# ADS8866.net
KiCad netlist of a schematic drawn in Altium Designer
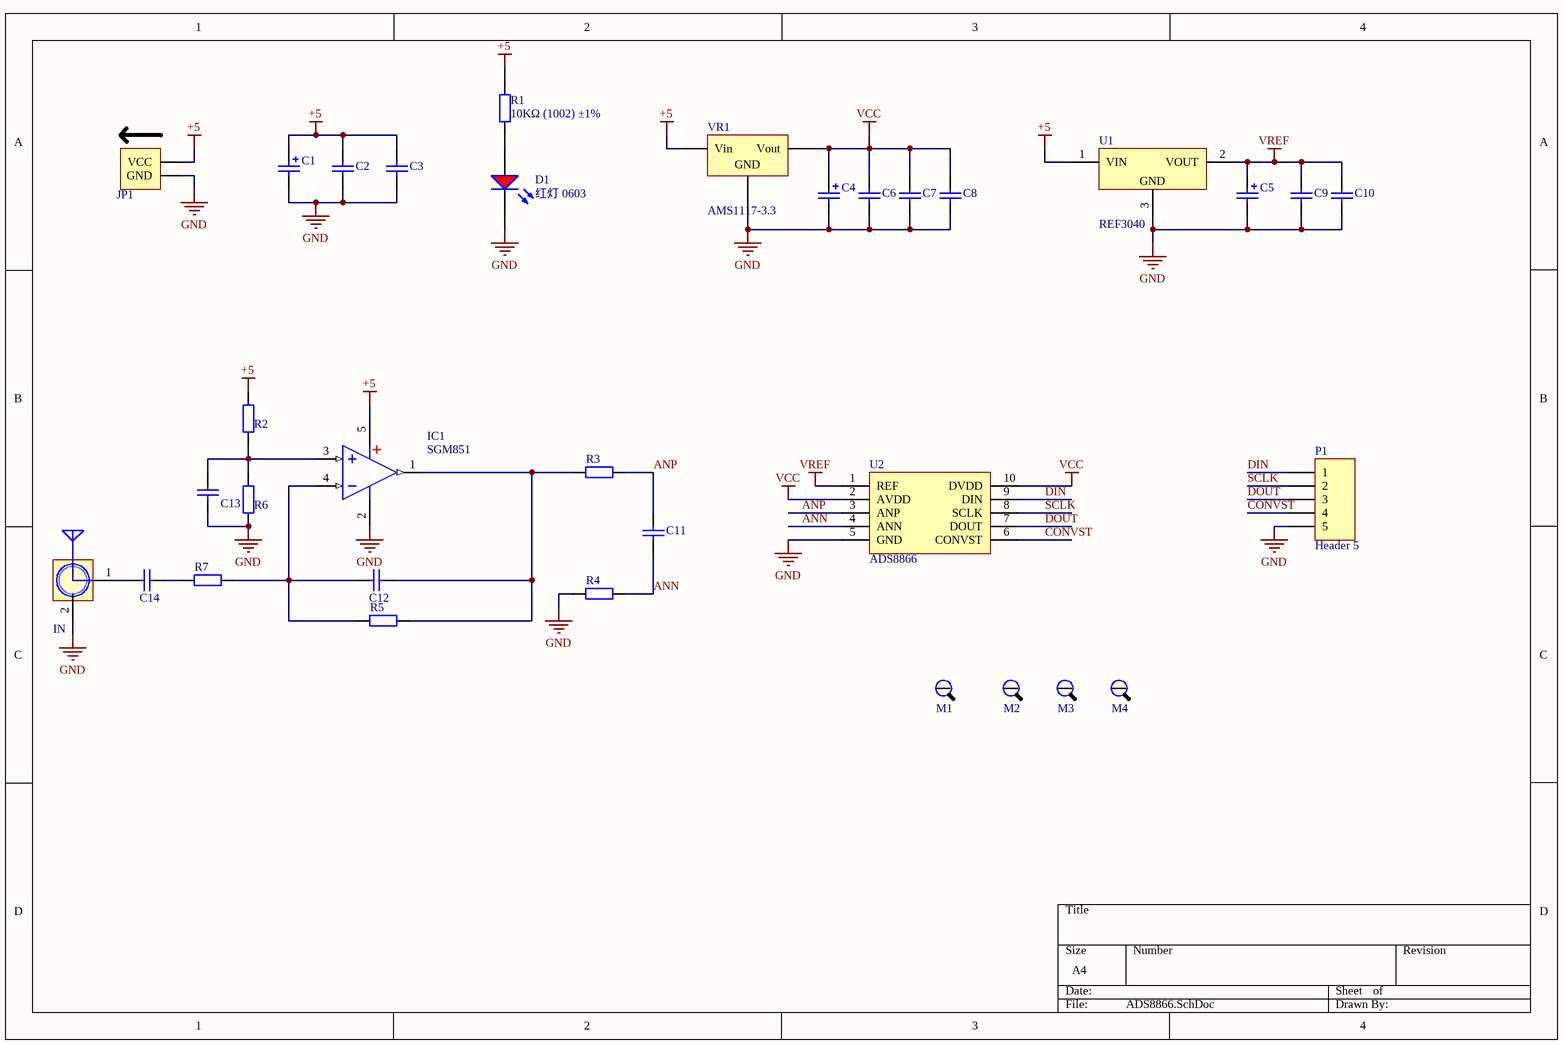
[diagram p0: ADS8866.SchDoc]

(export (version "E")
  (design (tool "Eeschema 10.0.6"))
  (components
    (comp (ref "C1")
      (value "10uF (106) ±10% 16V")
      (footprint "CASE-A_3216")
      (description "钽电容")
      (libsource (lib "JLC") (part "3216 10uF (106) 10% 16V"))
    )
    (comp (ref "C2")
      (value "100nF (104) 10% 50V")
      (footprint "0603_C")
      (description "贴片电容")
      (libsource (lib "JLC") (part "0603 100nF (104) 10% 50V"))
    )
    (comp (ref "C3")
      (value "100nF (104) 10% 50V")
      (footprint "0603_C")
      (description "贴片电容")
      (libsource (lib "JLC") (part "0603 100nF (104) 10% 50V"))
    )
    (comp (ref "C4")
      (value "10uF (106) ±10% 16V")
      (footprint "CASE-A_3216")
      (description "钽电容")
      (libsource (lib "JLC") (part "3216 10uF (106) 10% 16V"))
    )
    (comp (ref "C5")
      (value "10uF (106) ±10% 16V")
      (footprint "CASE-A_3216")
      (description "钽电容")
      (libsource (lib "JLC") (part "3216 10uF (106) 10% 16V"))
    )
    (comp (ref "C6")
      (value "100nF (104) 10% 50V")
      (footprint "0603_C")
      (description "贴片电容")
      (libsource (lib "JLC") (part "0603 100nF (104) 10% 50V"))
    )
    (comp (ref "C7")
      (value "100nF (104) 10% 50V")
      (footprint "0603_C")
      (description "贴片电容")
      (libsource (lib "JLC") (part "0603 100nF (104) 10% 50V"))
    )
    (comp (ref "C8")
      (value "100nF (104) 10% 50V")
      (footprint "0603_C")
      (description "贴片电容")
      (libsource (lib "JLC") (part "0603 100nF (104) 10% 50V"))
    )
    (comp (ref "C9")
      (value "100nF (104) 10% 50V")
      (footprint "0603_C")
      (description "贴片电容")
      (libsource (lib "JLC") (part "0603 100nF (104) 10% 50V"))
    )
    (comp (ref "C10")
      (value "100nF (104) 10% 50V")
      (footprint "0603_C")
      (description "贴片电容")
      (libsource (lib "JLC") (part "0603 100nF (104) 10% 50V"))
    )
    (comp (ref "C11")
      (value "1.5nF (152) 10% 50V")
      (footprint "0603_C")
      (description "贴片电容")
      (libsource (lib "JLC") (part "0603 1.5nF (152) 10% 50V"))
    )
    (comp (ref "C12")
      (value "100nF (104) 10% 50V")
      (footprint "0603_C")
      (description "贴片电容")
      (libsource (lib "JLC") (part "0603 100nF (104) 10% 50V"))
    )
    (comp (ref "C13")
      (value "100nF (104) 10% 50V")
      (footprint "0603_C")
      (description "贴片电容")
      (libsource (lib "JLC") (part "0603 100nF (104) 10% 50V"))
    )
    (comp (ref "C14")
      (value "100nF (104) 10% 50V")
      (footprint "0603_C")
      (description "贴片电容")
      (libsource (lib "JLC") (part "0603 100nF (104) 10% 50V"))
    )
    (comp (ref "D1")
      (value "红灯 0603")
      (footprint "0603_LED_S1")
      (description "发光二极管")
      (libsource (lib "JLC") (part "0603 红灯"))
    )
    (comp (ref "IC1")
      (value "SGM851")
      (footprint "SOT23-5N")
      (description "SOT23-5_轨至轨运放")
      (fields (field (name "版权归属") "源创客"))
      (libsource (lib "1.5   - 运放-功放") (part "SGM8521-5Pin"))
    )
    (comp (ref "IN")
      (value "SMA WIFI 天线接口")
      (footprint "SMA")
      (description "SMA-2.4G射频天线接口")
      (fields (field (name "版权归属") "源创客"))
      (libsource (lib "Cooperation") (part "PORT_SMA"))
    )
    (comp (ref "JP1")
      (value "HDR-1X2")
      (footprint "Power_IN_3.81-2P")
      (description "2P接插件,模块单电源供电口")
      (fields (field (name "版权归属") "源创客"))
      (libsource (lib "Cooperation") (part "PORT_Power_IN2"))
    )
    (comp (ref "M1")
      (value "M3")
      (footprint "M3x10_L")
      (description "螺丝")
      (libsource (lib "Cooperation") (part "ELSE_M3_screw"))
    )
    (comp (ref "M2")
      (value "M3")
      (footprint "M3x10_L")
      (description "螺丝")
      (libsource (lib "Cooperation") (part "ELSE_M3_screw"))
    )
    (comp (ref "M3")
      (value "M3")
      (footprint "M3x10_L")
      (description "螺丝")
      (libsource (lib "Cooperation") (part "ELSE_M3_screw"))
    )
    (comp (ref "M4")
      (value "M3")
      (footprint "M3x10_L")
      (description "螺丝")
      (libsource (lib "Cooperation") (part "ELSE_M3_screw"))
    )
    (comp (ref "P1")
      (value "Header 5")
      (footprint "HDR1X5")
      (description "Header, 5-Pin")
      (fields (field (name "PUBLISHER") "Altium Limited"))
      (libsource (lib "Miscellaneous Connectors") (part "Header 5"))
    )
    (comp (ref "R1")
      (value "10KΩ (1002) ±1%")
      (footprint "0603_R")
      (description "贴片电阻")
      (libsource (lib "JLC") (part "0603 10KΩ (1002) 1%"))
    )
    (comp (ref "R2")
      (value "110Ω (1100) ±1%")
      (footprint "0603_R")
      (description "贴片电阻")
      (libsource (lib "") (part "0603 110Ω (1100) 1%_1"))
    )
    (comp (ref "R3")
      (value "110Ω (1100) ±1%")
      (footprint "0603_R")
      (description "贴片电阻")
      (libsource (lib "JLC") (part "0603 110Ω (1100) 1%"))
    )
    (comp (ref "R4")
      (value "110Ω (1100) ±1%")
      (footprint "0603_R")
      (description "贴片电阻")
      (libsource (lib "JLC") (part "0603 110Ω (1100) 1%"))
    )
    (comp (ref "R5")
      (value "110Ω (1100) ±1%")
      (footprint "0603_R")
      (description "贴片电阻")
      (libsource (lib "JLC") (part "0603 110Ω (1100) 1%"))
    )
    (comp (ref "R6")
      (value "110Ω (1100) ±1%")
      (footprint "0603_R")
      (description "贴片电阻")
      (libsource (lib "") (part "0603 110Ω (1100) 1%_1"))
    )
    (comp (ref "R7")
      (value "110Ω (1100) ±1%")
      (footprint "0603_R")
      (description "贴片电阻")
      (libsource (lib "JLC") (part "0603 110Ω (1100) 1%"))
    )
    (comp (ref "U1")
      (value "REF3040")
      (footprint "SOT23-3N")
      (libsource (lib "Cooperation") (part "REF3040"))
    )
    (comp (ref "U2")
      (value "ADS8866")
      (footprint "MSOP10_N")
      (libsource (lib "Cooperation") (part "ADS8866"))
    )
    (comp (ref "VR1")
      (value "AMS1117-3.3")
      (footprint "SOT-223")
      (description "低压差线性稳压(LDO)")
      (libsource (lib "JLC") (part "SOT-223 AMS1117-3.3"))
    )
  )
  (nets
    (net (code "1") (name "+5") (class "Default")
      (node (ref "C1") (pin "1") (pinfunction "1_1") (pintype "passive"))
      (node (ref "C2") (pin "2") (pinfunction "2_2") (pintype "passive"))
      (node (ref "C3") (pin "2") (pinfunction "2_2") (pintype "passive"))
      (node (ref "IC1") (pin "5") (pinfunction "V+_5") (pintype "power_in"))
      (node (ref "JP1") (pin "1") (pinfunction "VCC_1") (pintype "passive"))
      (node (ref "R1") (pin "2") (pinfunction "2_2") (pintype "passive"))
      (node (ref "R2") (pin "2") (pinfunction "2_2") (pintype "passive"))
      (node (ref "U1") (pin "1") (pinfunction "VIN_1") (pintype "passive"))
      (node (ref "VR1") (pin "3") (pinfunction "Vin_3") (pintype "passive"))
    )
    (net (code "2") (name "/ANN") (class "Default")
      (node (ref "C11") (pin "1") (pinfunction "1_1") (pintype "passive"))
      (node (ref "R4") (pin "2") (pinfunction "2_2") (pintype "passive"))
      (node (ref "U2") (pin "4") (pinfunction "ANN_4") (pintype "passive"))
    )
    (net (code "3") (name "/ANP") (class "Default")
      (node (ref "C11") (pin "2") (pinfunction "2_2") (pintype "passive"))
      (node (ref "R3") (pin "2") (pinfunction "2_2") (pintype "passive"))
      (node (ref "U2") (pin "3") (pinfunction "ANP_3") (pintype "passive"))
    )
    (net (code "4") (name "/CONVST") (class "Default")
      (node (ref "P1") (pin "4") (pinfunction "4_4") (pintype "passive"))
      (node (ref "U2") (pin "6") (pinfunction "CONVST_6") (pintype "passive"))
    )
    (net (code "5") (name "/DIN") (class "Default")
      (node (ref "P1") (pin "1") (pinfunction "1_1") (pintype "passive"))
      (node (ref "U2") (pin "9") (pinfunction "DIN_9") (pintype "passive"))
    )
    (net (code "6") (name "/DOUT") (class "Default")
      (node (ref "P1") (pin "3") (pinfunction "3_3") (pintype "passive"))
      (node (ref "U2") (pin "7") (pinfunction "DOUT_7") (pintype "passive"))
    )
    (net (code "7") (name "/SCLK") (class "Default")
      (node (ref "P1") (pin "2") (pinfunction "2_2") (pintype "passive"))
      (node (ref "U2") (pin "8") (pinfunction "SCLK_8") (pintype "passive"))
    )
    (net (code "8") (name "GND") (class "Default")
      (node (ref "C1") (pin "2") (pinfunction "2_2") (pintype "passive"))
      (node (ref "C10") (pin "1") (pinfunction "1_1") (pintype "passive"))
      (node (ref "C13") (pin "2") (pinfunction "2_2") (pintype "passive"))
      (node (ref "C2") (pin "1") (pinfunction "1_1") (pintype "passive"))
      (node (ref "C3") (pin "1") (pinfunction "1_1") (pintype "passive"))
      (node (ref "C4") (pin "2") (pinfunction "2_2") (pintype "passive"))
      (node (ref "C5") (pin "2") (pinfunction "2_2") (pintype "passive"))
      (node (ref "C6") (pin "1") (pinfunction "1_1") (pintype "passive"))
      (node (ref "C7") (pin "1") (pinfunction "1_1") (pintype "passive"))
      (node (ref "C8") (pin "1") (pinfunction "1_1") (pintype "passive"))
      (node (ref "C9") (pin "1") (pinfunction "1_1") (pintype "passive"))
      (node (ref "D1") (pin "K") (pinfunction "K_K") (pintype "passive"))
      (node (ref "IC1") (pin "2") (pinfunction "V-_2") (pintype "power_in"))
      (node (ref "IN") (pin "2") (pinfunction "2_2") (pintype "passive"))
      (node (ref "JP1") (pin "2") (pinfunction "GND_2") (pintype "passive"))
      (node (ref "P1") (pin "5") (pinfunction "5_5") (pintype "passive"))
      (node (ref "R4") (pin "1") (pinfunction "1_1") (pintype "passive"))
      (node (ref "R6") (pin "1") (pinfunction "1_1") (pintype "passive"))
      (node (ref "U1") (pin "3") (pinfunction "GND_3") (pintype "passive"))
      (node (ref "U2") (pin "5") (pinfunction "GND_5") (pintype "passive"))
      (node (ref "VR1") (pin "1") (pinfunction "GND_1") (pintype "passive"))
    )
    (net (code "9") (name "Net-(C14-Pad2)") (class "Default")
      (node (ref "C14") (pin "2") (pinfunction "2_2") (pintype "passive"))
      (node (ref "R7") (pin "1") (pinfunction "1_1") (pintype "passive"))
    )
    (net (code "10") (name "Net-(D1-PadA)") (class "Default")
      (node (ref "D1") (pin "A") (pinfunction "A_A") (pintype "passive"))
      (node (ref "R1") (pin "1") (pinfunction "1_1") (pintype "passive"))
    )
    (net (code "11") (name "Net-(IC1-IN+)") (class "Default")
      (node (ref "C13") (pin "1") (pinfunction "1_1") (pintype "passive"))
      (node (ref "IC1") (pin "3") (pinfunction "IN+_3") (pintype "input"))
      (node (ref "R2") (pin "1") (pinfunction "1_1") (pintype "passive"))
      (node (ref "R6") (pin "2") (pinfunction "2_2") (pintype "passive"))
    )
    (net (code "12") (name "Net-(IC1-IN-)") (class "Default")
      (node (ref "C12") (pin "2") (pinfunction "2_2") (pintype "passive"))
      (node (ref "IC1") (pin "4") (pinfunction "IN-_4") (pintype "input"))
      (node (ref "R5") (pin "1") (pinfunction "1_1") (pintype "passive"))
      (node (ref "R7") (pin "2") (pinfunction "2_2") (pintype "passive"))
    )
    (net (code "13") (name "Net-(IC1-OUT)") (class "Default")
      (node (ref "C12") (pin "1") (pinfunction "1_1") (pintype "passive"))
      (node (ref "IC1") (pin "1") (pinfunction "OUT_1") (pintype "output"))
      (node (ref "R3") (pin "1") (pinfunction "1_1") (pintype "passive"))
      (node (ref "R5") (pin "2") (pinfunction "2_2") (pintype "passive"))
    )
    (net (code "14") (name "Net-(IN-SINGLE)") (class "Default")
      (node (ref "C14") (pin "1") (pinfunction "1_1") (pintype "passive"))
      (node (ref "IN") (pin "1") (pinfunction "SINGLE_1") (pintype "passive"))
    )
    (net (code "15") (name "VCC") (class "Default")
      (node (ref "C4") (pin "1") (pinfunction "1_1") (pintype "passive"))
      (node (ref "C6") (pin "2") (pinfunction "2_2") (pintype "passive"))
      (node (ref "C7") (pin "2") (pinfunction "2_2") (pintype "passive"))
      (node (ref "C8") (pin "2") (pinfunction "2_2") (pintype "passive"))
      (node (ref "U2") (pin "10") (pinfunction "DVDD_10") (pintype "passive"))
      (node (ref "U2") (pin "2") (pinfunction "AVDD_2") (pintype "passive"))
      (node (ref "VR1") (pin "2") (pinfunction "Vout_2") (pintype "passive"))
    )
    (net (code "16") (name "VREF") (class "Default")
      (node (ref "C10") (pin "2") (pinfunction "2_2") (pintype "passive"))
      (node (ref "C5") (pin "1") (pinfunction "1_1") (pintype "passive"))
      (node (ref "C9") (pin "2") (pinfunction "2_2") (pintype "passive"))
      (node (ref "U1") (pin "2") (pinfunction "VOUT_2") (pintype "passive"))
      (node (ref "U2") (pin "1") (pinfunction "REF_1") (pintype "passive"))
    )
    (net (code "17") (name "unconnected-(M1-Pad1)") (class "Default")
      (node (ref "M1") (pin "1") (pinfunction "1_1") (pintype "passive"))
    )
    (net (code "18") (name "unconnected-(M2-Pad1)") (class "Default")
      (node (ref "M2") (pin "1") (pinfunction "1_1") (pintype "passive"))
    )
    (net (code "19") (name "unconnected-(M3-Pad1)") (class "Default")
      (node (ref "M3") (pin "1") (pinfunction "1_1") (pintype "passive"))
    )
    (net (code "20") (name "unconnected-(M4-Pad1)") (class "Default")
      (node (ref "M4") (pin "1") (pinfunction "1_1") (pintype "passive"))
    )
  )
)
